# 01_mcu.net
KiCad netlist of a schematic drawn in Altium Designer
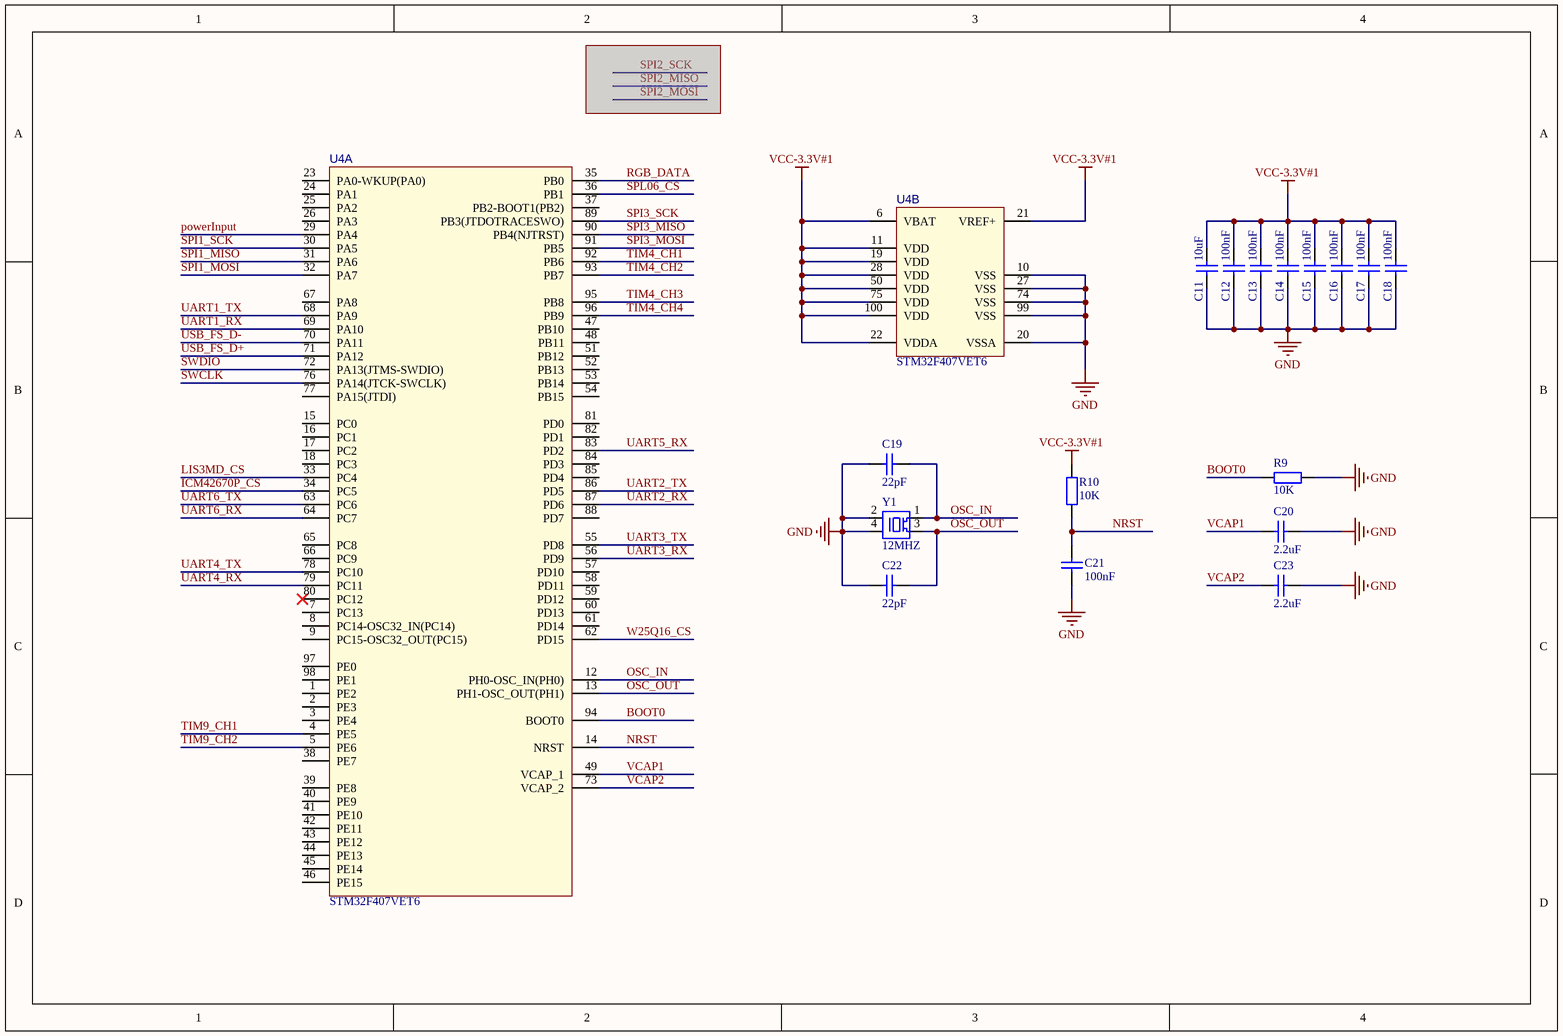
[diagram p0: 01_mcu.SchDoc]

(export (version "E")
  (design (tool "Eeschema 10.0.6"))
  (components
    (comp (ref "C11")
      (value "10uF")
      (footprint "0603-C")
      (description "贴片电容")
      (libsource (lib "封装库") (part "C"))
    )
    (comp (ref "C12")
      (value "100nF")
      (footprint "0603-C")
      (description "贴片电容")
      (libsource (lib "封装库") (part "C"))
    )
    (comp (ref "C13")
      (value "100nF")
      (footprint "0603-C")
      (description "贴片电容")
      (libsource (lib "封装库") (part "C"))
    )
    (comp (ref "C14")
      (value "100nF")
      (footprint "0603-C")
      (description "贴片电容")
      (libsource (lib "封装库") (part "C"))
    )
    (comp (ref "C15")
      (value "100nF")
      (footprint "0603-C")
      (description "贴片电容")
      (libsource (lib "封装库") (part "C"))
    )
    (comp (ref "C16")
      (value "100nF")
      (footprint "0603-C")
      (description "贴片电容")
      (libsource (lib "封装库") (part "C"))
    )
    (comp (ref "C17")
      (value "100nF")
      (footprint "0603-C")
      (description "贴片电容")
      (libsource (lib "封装库") (part "C"))
    )
    (comp (ref "C18")
      (value "100nF")
      (footprint "0603-C")
      (description "贴片电容")
      (libsource (lib "封装库") (part "C"))
    )
    (comp (ref "C19")
      (value "22pF")
      (footprint "0603-C")
      (description "贴片电容")
      (libsource (lib "封装库") (part "C"))
    )
    (comp (ref "C20")
      (value "2.2uF")
      (footprint "0603-C")
      (description "贴片电容")
      (libsource (lib "封装库") (part "C"))
    )
    (comp (ref "C21")
      (value "100nF")
      (footprint "0603-C")
      (description "贴片电容")
      (libsource (lib "封装库") (part "C"))
    )
    (comp (ref "C22")
      (value "22pF")
      (footprint "0603-C")
      (description "贴片电容")
      (libsource (lib "封装库") (part "C"))
    )
    (comp (ref "C23")
      (value "2.2uF")
      (footprint "0603-C")
      (description "贴片电容")
      (libsource (lib "封装库") (part "C"))
    )
    (comp (ref "R9")
      (value "10K")
      (footprint "0603-R")
      (description "贴片电阻")
      (libsource (lib "封装库") (part "R"))
    )
    (comp (ref "R10")
      (value "10K")
      (footprint "0603-R")
      (description "贴片电阻")
      (libsource (lib "封装库") (part "R"))
    )
    (comp (ref "U4")
      (value "STM32F407VET6")
      (footprint "STM32F407VET6")
      (fields (field (name "MANUFACTURER") "ST(意法半导体)"))
      (libsource (lib "封装库") (part "STM32F407VET6"))
    )
    (comp (ref "Y1")
      (value "12MHZ")
      (footprint "3225")
      (description "无源晶振")
      (libsource (lib "数传模块") (part "Y"))
    )
  )
  (nets
    (net (code "1") (name "/BOOT0") (class "Default")
      (node (ref "R9") (pin "2") (pinfunction "2_2") (pintype "passive"))
      (node (ref "U4") (pin "94") (pinfunction "BOOT0_94") (pintype "passive"))
    )
    (net (code "2") (name "/ICM42670P_CS") (class "Default")
      (node (ref "U4") (pin "34") (pinfunction "PC5_34") (pintype "passive"))
    )
    (net (code "3") (name "/LIS3MD_CS") (class "Default")
      (node (ref "U4") (pin "33") (pinfunction "PC4_33") (pintype "passive"))
    )
    (net (code "4") (name "/NRST") (class "Default")
      (node (ref "C21") (pin "2") (pinfunction "2_2") (pintype "passive"))
      (node (ref "R10") (pin "1") (pinfunction "1_1") (pintype "passive"))
      (node (ref "U4") (pin "14") (pinfunction "NRST_14") (pintype "passive"))
    )
    (net (code "5") (name "/OSC_IN") (class "Default")
      (node (ref "C19") (pin "2") (pinfunction "2_2") (pintype "passive"))
      (node (ref "U4") (pin "12") (pinfunction "PH0-OSC_IN(PH0)_12") (pintype "passive"))
      (node (ref "Y1") (pin "1") (pinfunction "XTAL1_1") (pintype "passive"))
    )
    (net (code "6") (name "/OSC_OUT") (class "Default")
      (node (ref "C22") (pin "2") (pinfunction "2_2") (pintype "passive"))
      (node (ref "U4") (pin "13") (pinfunction "PH1-OSC_OUT(PH1)_13") (pintype "passive"))
      (node (ref "Y1") (pin "3") (pinfunction "XTAL3_3") (pintype "passive"))
    )
    (net (code "7") (name "/RGB_DATA") (class "Default")
      (node (ref "U4") (pin "35") (pinfunction "PB0_35") (pintype "passive"))
    )
    (net (code "8") (name "/SPI1_MISO") (class "Default")
      (node (ref "U4") (pin "31") (pinfunction "PA6_31") (pintype "passive"))
    )
    (net (code "9") (name "/SPI1_MOSI") (class "Default")
      (node (ref "U4") (pin "32") (pinfunction "PA7_32") (pintype "passive"))
    )
    (net (code "10") (name "/SPI1_SCK") (class "Default")
      (node (ref "U4") (pin "30") (pinfunction "PA5_30") (pintype "passive"))
    )
    (net (code "14") (name "/SPI3_MISO") (class "Default")
      (node (ref "U4") (pin "90") (pinfunction "PB4(NJTRST)_90") (pintype "passive"))
    )
    (net (code "15") (name "/SPI3_MOSI") (class "Default")
      (node (ref "U4") (pin "91") (pinfunction "PB5_91") (pintype "passive"))
    )
    (net (code "16") (name "/SPI3_SCK") (class "Default")
      (node (ref "U4") (pin "89") (pinfunction "PB3(JTDOTRACESWO)_89") (pintype "passive"))
    )
    (net (code "17") (name "/SPL06_CS") (class "Default")
      (node (ref "U4") (pin "36") (pinfunction "PB1_36") (pintype "passive"))
    )
    (net (code "18") (name "/SWCLK") (class "Default")
      (node (ref "U4") (pin "76") (pinfunction "PA14(JTCK-SWCLK)_76") (pintype "passive"))
    )
    (net (code "19") (name "/SWDIO") (class "Default")
      (node (ref "U4") (pin "72") (pinfunction "PA13(JTMS-SWDIO)_72") (pintype "passive"))
    )
    (net (code "20") (name "/TIM4_CH1") (class "Default")
      (node (ref "U4") (pin "92") (pinfunction "PB6_92") (pintype "passive"))
    )
    (net (code "21") (name "/TIM4_CH2") (class "Default")
      (node (ref "U4") (pin "93") (pinfunction "PB7_93") (pintype "passive"))
    )
    (net (code "22") (name "/TIM4_CH3") (class "Default")
      (node (ref "U4") (pin "95") (pinfunction "PB8_95") (pintype "passive"))
    )
    (net (code "23") (name "/TIM4_CH4") (class "Default")
      (node (ref "U4") (pin "96") (pinfunction "PB9_96") (pintype "passive"))
    )
    (net (code "24") (name "/TIM9_CH1") (class "Default")
      (node (ref "U4") (pin "4") (pinfunction "PE5_4") (pintype "passive"))
    )
    (net (code "25") (name "/TIM9_CH2") (class "Default")
      (node (ref "U4") (pin "5") (pinfunction "PE6_5") (pintype "passive"))
    )
    (net (code "26") (name "/UART1_RX") (class "Default")
      (node (ref "U4") (pin "69") (pinfunction "PA10_69") (pintype "passive"))
    )
    (net (code "27") (name "/UART1_TX") (class "Default")
      (node (ref "U4") (pin "68") (pinfunction "PA9_68") (pintype "passive"))
    )
    (net (code "28") (name "/UART2_RX") (class "Default")
      (node (ref "U4") (pin "87") (pinfunction "PD6_87") (pintype "passive"))
    )
    (net (code "29") (name "/UART2_TX") (class "Default")
      (node (ref "U4") (pin "86") (pinfunction "PD5_86") (pintype "passive"))
    )
    (net (code "30") (name "/UART3_RX") (class "Default")
      (node (ref "U4") (pin "56") (pinfunction "PD9_56") (pintype "passive"))
    )
    (net (code "31") (name "/UART3_TX") (class "Default")
      (node (ref "U4") (pin "55") (pinfunction "PD8_55") (pintype "passive"))
    )
    (net (code "32") (name "/UART4_RX") (class "Default")
      (node (ref "U4") (pin "79") (pinfunction "PC11_79") (pintype "passive"))
    )
    (net (code "33") (name "/UART4_TX") (class "Default")
      (node (ref "U4") (pin "78") (pinfunction "PC10_78") (pintype "passive"))
    )
    (net (code "34") (name "/UART5_RX") (class "Default")
      (node (ref "U4") (pin "83") (pinfunction "PD2_83") (pintype "passive"))
    )
    (net (code "35") (name "/UART6_RX") (class "Default")
      (node (ref "U4") (pin "64") (pinfunction "PC7_64") (pintype "passive"))
    )
    (net (code "36") (name "/UART6_TX") (class "Default")
      (node (ref "U4") (pin "63") (pinfunction "PC6_63") (pintype "passive"))
    )
    (net (code "37") (name "/USB_FS_D+") (class "Default")
      (node (ref "U4") (pin "71") (pinfunction "PA12_71") (pintype "passive"))
    )
    (net (code "38") (name "/USB_FS_D-") (class "Default")
      (node (ref "U4") (pin "70") (pinfunction "PA11_70") (pintype "passive"))
    )
    (net (code "39") (name "/VCAP1") (class "Default")
      (node (ref "C20") (pin "1") (pinfunction "1_1") (pintype "passive"))
      (node (ref "U4") (pin "49") (pinfunction "VCAP_1_49") (pintype "passive"))
    )
    (net (code "40") (name "/VCAP2") (class "Default")
      (node (ref "C23") (pin "1") (pinfunction "1_1") (pintype "passive"))
      (node (ref "U4") (pin "73") (pinfunction "VCAP_2_73") (pintype "passive"))
    )
    (net (code "41") (name "/W25Q16_CS") (class "Default")
      (node (ref "U4") (pin "62") (pinfunction "PD15_62") (pintype "passive"))
    )
    (net (code "42") (name "/powerInput") (class "Default")
      (node (ref "U4") (pin "29") (pinfunction "PA4_29") (pintype "passive"))
    )
    (net (code "43") (name "GND") (class "Default")
      (node (ref "C11") (pin "1") (pinfunction "1_1") (pintype "passive"))
      (node (ref "C12") (pin "1") (pinfunction "1_1") (pintype "passive"))
      (node (ref "C13") (pin "1") (pinfunction "1_1") (pintype "passive"))
      (node (ref "C14") (pin "1") (pinfunction "1_1") (pintype "passive"))
      (node (ref "C15") (pin "1") (pinfunction "1_1") (pintype "passive"))
      (node (ref "C16") (pin "1") (pinfunction "1_1") (pintype "passive"))
      (node (ref "C17") (pin "1") (pinfunction "1_1") (pintype "passive"))
      (node (ref "C18") (pin "1") (pinfunction "1_1") (pintype "passive"))
      (node (ref "C19") (pin "1") (pinfunction "1_1") (pintype "passive"))
      (node (ref "C20") (pin "2") (pinfunction "2_2") (pintype "passive"))
      (node (ref "C21") (pin "1") (pinfunction "1_1") (pintype "passive"))
      (node (ref "C22") (pin "1") (pinfunction "1_1") (pintype "passive"))
      (node (ref "C23") (pin "2") (pinfunction "2_2") (pintype "passive"))
      (node (ref "R9") (pin "1") (pinfunction "1_1") (pintype "passive"))
      (node (ref "U4") (pin "10") (pinfunction "VSS_10") (pintype "passive"))
      (node (ref "U4") (pin "20") (pinfunction "VSSA_20") (pintype "passive"))
      (node (ref "U4") (pin "27") (pinfunction "VSS_27") (pintype "passive"))
      (node (ref "U4") (pin "74") (pinfunction "VSS_74") (pintype "passive"))
      (node (ref "U4") (pin "99") (pinfunction "VSS_99") (pintype "passive"))
      (node (ref "Y1") (pin "2") (pinfunction "GND_2") (pintype "passive"))
      (node (ref "Y1") (pin "4") (pinfunction "GND_4") (pintype "passive"))
    )
    (net (code "44") (name "VCC-3.3V#1") (class "Default")
      (node (ref "C11") (pin "2") (pinfunction "2_2") (pintype "passive"))
      (node (ref "C12") (pin "2") (pinfunction "2_2") (pintype "passive"))
      (node (ref "C13") (pin "2") (pinfunction "2_2") (pintype "passive"))
      (node (ref "C14") (pin "2") (pinfunction "2_2") (pintype "passive"))
      (node (ref "C15") (pin "2") (pinfunction "2_2") (pintype "passive"))
      (node (ref "C16") (pin "2") (pinfunction "2_2") (pintype "passive"))
      (node (ref "C17") (pin "2") (pinfunction "2_2") (pintype "passive"))
      (node (ref "C18") (pin "2") (pinfunction "2_2") (pintype "passive"))
      (node (ref "R10") (pin "2") (pinfunction "2_2") (pintype "passive"))
      (node (ref "U4") (pin "100") (pinfunction "VDD_100") (pintype "passive"))
      (node (ref "U4") (pin "11") (pinfunction "VDD_11") (pintype "passive"))
      (node (ref "U4") (pin "19") (pinfunction "VDD_19") (pintype "passive"))
      (node (ref "U4") (pin "21") (pinfunction "VREF+_21") (pintype "passive"))
      (node (ref "U4") (pin "22") (pinfunction "VDDA_22") (pintype "passive"))
      (node (ref "U4") (pin "28") (pinfunction "VDD_28") (pintype "passive"))
      (node (ref "U4") (pin "50") (pinfunction "VDD_50") (pintype "passive"))
      (node (ref "U4") (pin "6") (pinfunction "VBAT_6") (pintype "passive"))
      (node (ref "U4") (pin "75") (pinfunction "VDD_75") (pintype "passive"))
    )
    (net (code "45") (name "unconnected-(U4A-PA0-WKUP(PA0)-Pad23)") (class "Default")
      (node (ref "U4") (pin "23") (pinfunction "PA0-WKUP(PA0)_23") (pintype "passive"))
    )
    (net (code "46") (name "unconnected-(U4A-PA1-Pad24)") (class "Default")
      (node (ref "U4") (pin "24") (pinfunction "PA1_24") (pintype "passive"))
    )
    (net (code "47") (name "unconnected-(U4A-PA2-Pad25)") (class "Default")
      (node (ref "U4") (pin "25") (pinfunction "PA2_25") (pintype "passive"))
    )
    (net (code "48") (name "unconnected-(U4A-PA3-Pad26)") (class "Default")
      (node (ref "U4") (pin "26") (pinfunction "PA3_26") (pintype "passive"))
    )
    (net (code "49") (name "unconnected-(U4A-PA8-Pad67)") (class "Default")
      (node (ref "U4") (pin "67") (pinfunction "PA8_67") (pintype "passive"))
    )
    (net (code "50") (name "unconnected-(U4A-PA15(JTDI)-Pad77)") (class "Default")
      (node (ref "U4") (pin "77") (pinfunction "PA15(JTDI)_77") (pintype "passive"))
    )
    (net (code "51") (name "unconnected-(U4A-PB2-BOOT1(PB2)-Pad37)") (class "Default")
      (node (ref "U4") (pin "37") (pinfunction "PB2-BOOT1(PB2)_37") (pintype "passive"))
    )
    (net (code "52") (name "unconnected-(U4A-PB10-Pad47)") (class "Default")
      (node (ref "U4") (pin "47") (pinfunction "PB10_47") (pintype "passive"))
    )
    (net (code "53") (name "unconnected-(U4A-PB11-Pad48)") (class "Default")
      (node (ref "U4") (pin "48") (pinfunction "PB11_48") (pintype "passive"))
    )
    (net (code "54") (name "unconnected-(U4A-PB12-Pad51)") (class "Default")
      (node (ref "U4") (pin "51") (pinfunction "PB12_51") (pintype "passive"))
    )
    (net (code "55") (name "unconnected-(U4A-PB13-Pad52)") (class "Default")
      (node (ref "U4") (pin "52") (pinfunction "PB13_52") (pintype "passive"))
    )
    (net (code "56") (name "unconnected-(U4A-PB14-Pad53)") (class "Default")
      (node (ref "U4") (pin "53") (pinfunction "PB14_53") (pintype "passive"))
    )
    (net (code "57") (name "unconnected-(U4A-PB15-Pad54)") (class "Default")
      (node (ref "U4") (pin "54") (pinfunction "PB15_54") (pintype "passive"))
    )
    (net (code "58") (name "unconnected-(U4A-PC0-Pad15)") (class "Default")
      (node (ref "U4") (pin "15") (pinfunction "PC0_15") (pintype "passive"))
    )
    (net (code "59") (name "unconnected-(U4A-PC1-Pad16)") (class "Default")
      (node (ref "U4") (pin "16") (pinfunction "PC1_16") (pintype "passive"))
    )
    (net (code "60") (name "unconnected-(U4A-PC2-Pad17)") (class "Default")
      (node (ref "U4") (pin "17") (pinfunction "PC2_17") (pintype "passive"))
    )
    (net (code "61") (name "unconnected-(U4A-PC3-Pad18)") (class "Default")
      (node (ref "U4") (pin "18") (pinfunction "PC3_18") (pintype "passive"))
    )
    (net (code "62") (name "unconnected-(U4A-PC8-Pad65)") (class "Default")
      (node (ref "U4") (pin "65") (pinfunction "PC8_65") (pintype "passive"))
    )
    (net (code "63") (name "unconnected-(U4A-PC9-Pad66)") (class "Default")
      (node (ref "U4") (pin "66") (pinfunction "PC9_66") (pintype "passive"))
    )
    (net (code "64") (name "unconnected-(U4A-PC12-Pad80)") (class "Default")
      (node (ref "U4") (pin "80") (pinfunction "PC12_80") (pintype "passive+no_connect"))
    )
    (net (code "65") (name "unconnected-(U4A-PC13-Pad7)") (class "Default")
      (node (ref "U4") (pin "7") (pinfunction "PC13_7") (pintype "passive"))
    )
    (net (code "66") (name "unconnected-(U4A-PC14-OSC32_IN(PC14)-Pad8)") (class "Default")
      (node (ref "U4") (pin "8") (pinfunction "PC14-OSC32_IN(PC14)_8") (pintype "passive"))
    )
    (net (code "67") (name "unconnected-(U4A-PC15-OSC32_OUT(PC15)-Pad9)") (class "Default")
      (node (ref "U4") (pin "9") (pinfunction "PC15-OSC32_OUT(PC15)_9") (pintype "passive"))
    )
    (net (code "68") (name "unconnected-(U4A-PD0-Pad81)") (class "Default")
      (node (ref "U4") (pin "81") (pinfunction "PD0_81") (pintype "passive"))
    )
    (net (code "69") (name "unconnected-(U4A-PD1-Pad82)") (class "Default")
      (node (ref "U4") (pin "82") (pinfunction "PD1_82") (pintype "passive"))
    )
    (net (code "70") (name "unconnected-(U4A-PD3-Pad84)") (class "Default")
      (node (ref "U4") (pin "84") (pinfunction "PD3_84") (pintype "passive"))
    )
    (net (code "71") (name "unconnected-(U4A-PD4-Pad85)") (class "Default")
      (node (ref "U4") (pin "85") (pinfunction "PD4_85") (pintype "passive"))
    )
    (net (code "72") (name "unconnected-(U4A-PD7-Pad88)") (class "Default")
      (node (ref "U4") (pin "88") (pinfunction "PD7_88") (pintype "passive"))
    )
    (net (code "73") (name "unconnected-(U4A-PD10-Pad57)") (class "Default")
      (node (ref "U4") (pin "57") (pinfunction "PD10_57") (pintype "passive"))
    )
    (net (code "74") (name "unconnected-(U4A-PD11-Pad58)") (class "Default")
      (node (ref "U4") (pin "58") (pinfunction "PD11_58") (pintype "passive"))
    )
    (net (code "75") (name "unconnected-(U4A-PD12-Pad59)") (class "Default")
      (node (ref "U4") (pin "59") (pinfunction "PD12_59") (pintype "passive"))
    )
    (net (code "76") (name "unconnected-(U4A-PD13-Pad60)") (class "Default")
      (node (ref "U4") (pin "60") (pinfunction "PD13_60") (pintype "passive"))
    )
    (net (code "77") (name "unconnected-(U4A-PD14-Pad61)") (class "Default")
      (node (ref "U4") (pin "61") (pinfunction "PD14_61") (pintype "passive"))
    )
    (net (code "78") (name "unconnected-(U4A-PE0-Pad97)") (class "Default")
      (node (ref "U4") (pin "97") (pinfunction "PE0_97") (pintype "passive"))
    )
    (net (code "79") (name "unconnected-(U4A-PE1-Pad98)") (class "Default")
      (node (ref "U4") (pin "98") (pinfunction "PE1_98") (pintype "passive"))
    )
    (net (code "80") (name "unconnected-(U4A-PE2-Pad1)") (class "Default")
      (node (ref "U4") (pin "1") (pinfunction "PE2_1") (pintype "passive"))
    )
    (net (code "81") (name "unconnected-(U4A-PE3-Pad2)") (class "Default")
      (node (ref "U4") (pin "2") (pinfunction "PE3_2") (pintype "passive"))
    )
    (net (code "82") (name "unconnected-(U4A-PE4-Pad3)") (class "Default")
      (node (ref "U4") (pin "3") (pinfunction "PE4_3") (pintype "passive"))
    )
    (net (code "83") (name "unconnected-(U4A-PE7-Pad38)") (class "Default")
      (node (ref "U4") (pin "38") (pinfunction "PE7_38") (pintype "passive"))
    )
    (net (code "84") (name "unconnected-(U4A-PE8-Pad39)") (class "Default")
      (node (ref "U4") (pin "39") (pinfunction "PE8_39") (pintype "passive"))
    )
    (net (code "85") (name "unconnected-(U4A-PE9-Pad40)") (class "Default")
      (node (ref "U4") (pin "40") (pinfunction "PE9_40") (pintype "passive"))
    )
    (net (code "86") (name "unconnected-(U4A-PE10-Pad41)") (class "Default")
      (node (ref "U4") (pin "41") (pinfunction "PE10_41") (pintype "passive"))
    )
    (net (code "87") (name "unconnected-(U4A-PE11-Pad42)") (class "Default")
      (node (ref "U4") (pin "42") (pinfunction "PE11_42") (pintype "passive"))
    )
    (net (code "88") (name "unconnected-(U4A-PE12-Pad43)") (class "Default")
      (node (ref "U4") (pin "43") (pinfunction "PE12_43") (pintype "passive"))
    )
    (net (code "89") (name "unconnected-(U4A-PE13-Pad44)") (class "Default")
      (node (ref "U4") (pin "44") (pinfunction "PE13_44") (pintype "passive"))
    )
    (net (code "90") (name "unconnected-(U4A-PE14-Pad45)") (class "Default")
      (node (ref "U4") (pin "45") (pinfunction "PE14_45") (pintype "passive"))
    )
    (net (code "91") (name "unconnected-(U4A-PE15-Pad46)") (class "Default")
      (node (ref "U4") (pin "46") (pinfunction "PE15_46") (pintype "passive"))
    )
  )
)
